# Power.net
KiCad netlist of a schematic drawn in Altium Designer
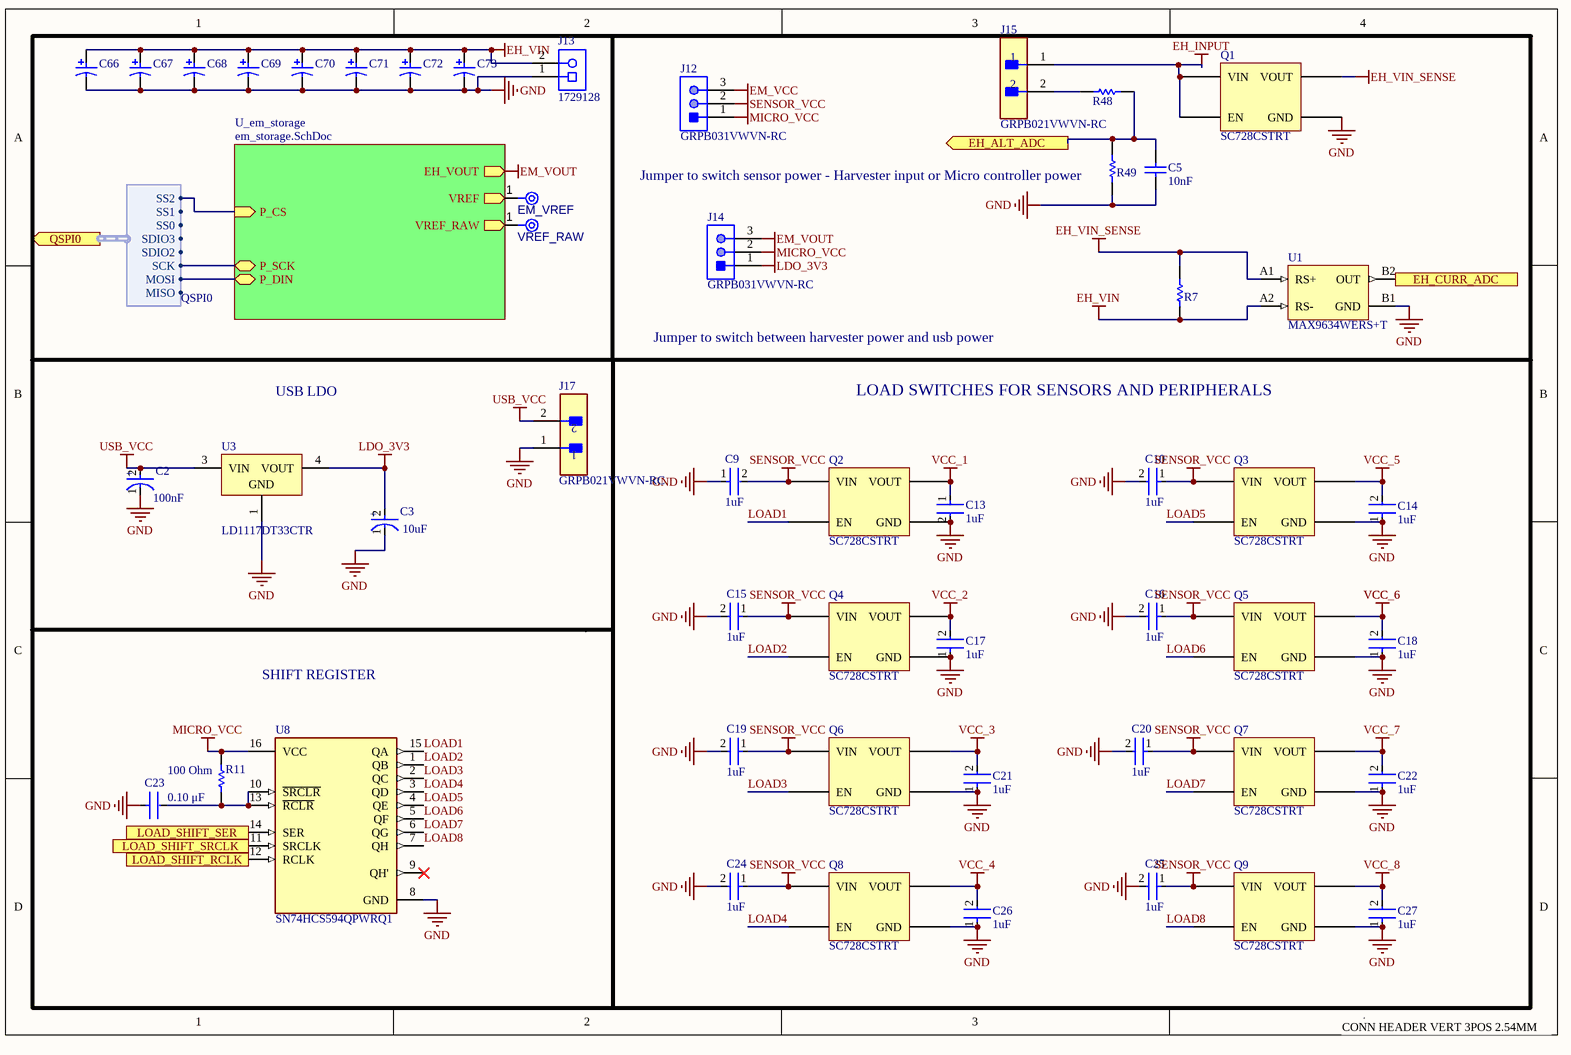
[diagram p0: Power.SchDoc]

(export (version "E")
  (design (tool "Eeschema 10.0.6"))
  (components
    (comp (ref "C2")
      (value "T491A104K035AT")
      (footprint "FP-T491A104K035AT-MFG")
      (description "CAP TANT 0.1UF 10% 35V 1206")
      (fields
        (field (name "TOLERANCE") "10%")
        (field (name "VOLTAGE") "35V")
        (field (name "CAPACITANCE") "100nF")
      )
      (libsource (lib "Altium Content Vault") (part "a00bbbee19879c290e62620ae7e47b1"))
    )
    (comp (ref "C3")
      (value "TAJA106K006RNJ")
      (footprint "FP-TAJA-MFG")
      (description "10uF 6.3V  ±10% 4Ω 1206  SMD Tantalum Capacitor")
      (fields
        (field (name "CAPACITANCE") "10uF")
        (field (name "VOLTAGE") "6.3V")
        (field (name "TOLERANCE") "20%")
      )
      (libsource (lib "Altium Content Vault") (part "203bc49f2ac43e59fd269a8c329ed05"))
    )
    (comp (ref "C5")
      (value "GRM188R71H103KA01D")
      (footprint "CAPC1608X90X35ML10T15")
      (description "Chip Capacitor, 10 nF, +/- 10%, 50 V, -55 to 125 degC, 0603 (1608 Metric), RoHS, Tape and Reel")
      (fields
        (field (name "VOLTAGE") "50V")
        (field (name "TOLERANCE") "10%")
        (field (name "CAPACITANCE") "10nF")
      )
      (libsource (lib "Altium Content Vault") (part "CAP-NP-2"))
    )
    (comp (ref "C9")
      (value "GRT155R61C105KE01J")
      (footprint "FP-GRM15-0_1-MFG")
      (description "CAP CER 1UF 10V X5R 0402")
      (fields
        (field (name "OCTOPART") "https://octopart.com/grm155r61a105ke15d-murata-197442")
        (field (name "MANUFACTURER PART NUMBER") "GRM155R61A105KE15D")
        (field (name "CAPACITANCE") "1uF")
      )
      (libsource (lib "Altium Content Vault") (part "02cd4be3c70576c341d710602a673aa"))
    )
    (comp (ref "C10")
      (value "GRT155R61C105KE01J")
      (footprint "FP-GRM15-0_1-MFG")
      (description "CAP CER 1UF 10V X5R 0402")
      (fields
        (field (name "OCTOPART") "https://octopart.com/grm155r61a105ke15d-murata-197442")
        (field (name "MANUFACTURER PART NUMBER") "GRM155R61A105KE15D")
        (field (name "CAPACITANCE") "1uF")
      )
      (libsource (lib "Altium Content Vault") (part "02cd4be3c70576c341d710602a673aa"))
    )
    (comp (ref "C13")
      (value "GRT155R61C105KE01J")
      (footprint "FP-GRM15-0_1-MFG")
      (description "CAP CER 1UF 10V X5R 0402")
      (fields
        (field (name "OCTOPART") "https://octopart.com/grm155r61a105ke15d-murata-197442")
        (field (name "MANUFACTURER PART NUMBER") "GRM155R61A105KE15D")
        (field (name "CAPACITANCE") "1uF")
      )
      (libsource (lib "Altium Content Vault") (part "02cd4be3c70576c341d710602a673aa"))
    )
    (comp (ref "C14")
      (value "GRT155R61C105KE01J")
      (footprint "FP-GRM15-0_1-MFG")
      (description "CAP CER 1UF 10V X5R 0402")
      (fields
        (field (name "OCTOPART") "https://octopart.com/grm155r61a105ke15d-murata-197442")
        (field (name "MANUFACTURER PART NUMBER") "GRM155R61A105KE15D")
        (field (name "CAPACITANCE") "1uF")
      )
      (libsource (lib "Altium Content Vault") (part "02cd4be3c70576c341d710602a673aa"))
    )
    (comp (ref "C15")
      (value "GRT155R61C105KE01J")
      (footprint "FP-GRM15-0_1-MFG")
      (description "CAP CER 1UF 10V X5R 0402")
      (fields
        (field (name "OCTOPART") "https://octopart.com/grm155r61a105ke15d-murata-197442")
        (field (name "MANUFACTURER PART NUMBER") "GRM155R61A105KE15D")
        (field (name "CAPACITANCE") "1uF")
      )
      (libsource (lib "Altium Content Vault") (part "02cd4be3c70576c341d710602a673aa"))
    )
    (comp (ref "C16")
      (value "GRT155R61C105KE01J")
      (footprint "FP-GRM15-0_1-MFG")
      (description "CAP CER 1UF 10V X5R 0402")
      (fields
        (field (name "OCTOPART") "https://octopart.com/grm155r61a105ke15d-murata-197442")
        (field (name "MANUFACTURER PART NUMBER") "GRM155R61A105KE15D")
        (field (name "CAPACITANCE") "1uF")
      )
      (libsource (lib "Altium Content Vault") (part "02cd4be3c70576c341d710602a673aa"))
    )
    (comp (ref "C17")
      (value "GRT155R61C105KE01J")
      (footprint "FP-GRM15-0_1-MFG")
      (description "CAP CER 1UF 10V X5R 0402")
      (fields
        (field (name "OCTOPART") "https://octopart.com/grm155r61a105ke15d-murata-197442")
        (field (name "MANUFACTURER PART NUMBER") "GRM155R61A105KE15D")
        (field (name "CAPACITANCE") "1uF")
      )
      (libsource (lib "Altium Content Vault") (part "02cd4be3c70576c341d710602a673aa"))
    )
    (comp (ref "C18")
      (value "GRT155R61C105KE01J")
      (footprint "FP-GRM15-0_1-MFG")
      (description "CAP CER 1UF 10V X5R 0402")
      (fields
        (field (name "OCTOPART") "https://octopart.com/grm155r61a105ke15d-murata-197442")
        (field (name "MANUFACTURER PART NUMBER") "GRM155R61A105KE15D")
        (field (name "CAPACITANCE") "1uF")
      )
      (libsource (lib "Altium Content Vault") (part "02cd4be3c70576c341d710602a673aa"))
    )
    (comp (ref "C19")
      (value "GRT155R61C105KE01J")
      (footprint "FP-GRM15-0_1-MFG")
      (description "CAP CER 1UF 10V X5R 0402")
      (fields
        (field (name "OCTOPART") "https://octopart.com/grm155r61a105ke15d-murata-197442")
        (field (name "MANUFACTURER PART NUMBER") "GRM155R61A105KE15D")
        (field (name "CAPACITANCE") "1uF")
      )
      (libsource (lib "Altium Content Vault") (part "02cd4be3c70576c341d710602a673aa"))
    )
    (comp (ref "C20")
      (value "GRT155R61C105KE01J")
      (footprint "FP-GRM15-0_1-MFG")
      (description "CAP CER 1UF 10V X5R 0402")
      (fields
        (field (name "OCTOPART") "https://octopart.com/grm155r61a105ke15d-murata-197442")
        (field (name "MANUFACTURER PART NUMBER") "GRM155R61A105KE15D")
        (field (name "CAPACITANCE") "1uF")
      )
      (libsource (lib "Altium Content Vault") (part "02cd4be3c70576c341d710602a673aa"))
    )
    (comp (ref "C21")
      (value "GRT155R61C105KE01J")
      (footprint "FP-GRM15-0_1-MFG")
      (description "CAP CER 1UF 10V X5R 0402")
      (fields
        (field (name "OCTOPART") "https://octopart.com/grm155r61a105ke15d-murata-197442")
        (field (name "MANUFACTURER PART NUMBER") "GRM155R61A105KE15D")
        (field (name "CAPACITANCE") "1uF")
      )
      (libsource (lib "Altium Content Vault") (part "02cd4be3c70576c341d710602a673aa"))
    )
    (comp (ref "C22")
      (value "GRT155R61C105KE01J")
      (footprint "FP-GRM15-0_1-MFG")
      (description "CAP CER 1UF 10V X5R 0402")
      (fields
        (field (name "OCTOPART") "https://octopart.com/grm155r61a105ke15d-murata-197442")
        (field (name "MANUFACTURER PART NUMBER") "GRM155R61A105KE15D")
        (field (name "CAPACITANCE") "1uF")
      )
      (libsource (lib "Altium Content Vault") (part "02cd4be3c70576c341d710602a673aa"))
    )
    (comp (ref "C23")
      (value "C0402C104K8PACTU")
      (footprint "FP-C0402-BB-MFG")
      (description "CAP CER 0.1UF 10V X5R 0402")
      (fields
        (field (name "CAPACITANCE") "0.10 μF")
        (field (name "MANUFACTURER") "Kemet")
        (field (name "TOLERANCE") "0.1")
      )
      (libsource (lib "Altium Content Vault") (part "b4654b650e69147ec39a6b967a45e02"))
    )
    (comp (ref "C24")
      (value "GRT155R61C105KE01J")
      (footprint "FP-GRM15-0_1-MFG")
      (description "CAP CER 1UF 10V X5R 0402")
      (fields
        (field (name "OCTOPART") "https://octopart.com/grm155r61a105ke15d-murata-197442")
        (field (name "MANUFACTURER PART NUMBER") "GRM155R61A105KE15D")
        (field (name "CAPACITANCE") "1uF")
      )
      (libsource (lib "Altium Content Vault") (part "02cd4be3c70576c341d710602a673aa"))
    )
    (comp (ref "C25")
      (value "GRT155R61C105KE01J")
      (footprint "FP-GRM15-0_1-MFG")
      (description "CAP CER 1UF 10V X5R 0402")
      (fields
        (field (name "OCTOPART") "https://octopart.com/grm155r61a105ke15d-murata-197442")
        (field (name "MANUFACTURER PART NUMBER") "GRM155R61A105KE15D")
        (field (name "CAPACITANCE") "1uF")
      )
      (libsource (lib "Altium Content Vault") (part "02cd4be3c70576c341d710602a673aa"))
    )
    (comp (ref "C26")
      (value "GRT155R61C105KE01J")
      (footprint "FP-GRM15-0_1-MFG")
      (description "CAP CER 1UF 10V X5R 0402")
      (fields
        (field (name "OCTOPART") "https://octopart.com/grm155r61a105ke15d-murata-197442")
        (field (name "MANUFACTURER PART NUMBER") "GRM155R61A105KE15D")
        (field (name "CAPACITANCE") "1uF")
      )
      (libsource (lib "Altium Content Vault") (part "02cd4be3c70576c341d710602a673aa"))
    )
    (comp (ref "C27")
      (value "GRT155R61C105KE01J")
      (footprint "FP-GRM15-0_1-MFG")
      (description "CAP CER 1UF 10V X5R 0402")
      (fields
        (field (name "OCTOPART") "https://octopart.com/grm155r61a105ke15d-murata-197442")
        (field (name "MANUFACTURER PART NUMBER") "GRM155R61A105KE15D")
        (field (name "CAPACITANCE") "1uF")
      )
      (libsource (lib "Altium Content Vault") (part "02cd4be3c70576c341d710602a673aa"))
    )
    (comp (ref "C66")
      (value "T491D106K025AT")
      (footprint "KEMT-T491-D_L")
      (description "Tantalum Capacitor, 10 uF, +/- 10%, 25 V, -55 to 125 degC, 2-Pin SMD, RoHS, Tape and Reel")
      (fields (field (name "MANUFACTURER") "Kemet") (field (name "VOLTAGE") "25VDC"))
      (libsource (lib "Altium Content Vault") (part "CAP-P-2"))
    )
    (comp (ref "C67")
      (value "T491D106K025AT")
      (footprint "KEMT-T491-D_L")
      (description "Tantalum Capacitor, 10 uF, +/- 10%, 25 V, -55 to 125 degC, 2-Pin SMD, RoHS, Tape and Reel")
      (fields (field (name "MANUFACTURER") "Kemet") (field (name "VOLTAGE") "25VDC"))
      (libsource (lib "Altium Content Vault") (part "CAP-P-2"))
    )
    (comp (ref "C68")
      (value "T491D106K025AT")
      (footprint "KEMT-T491-D_L")
      (description "Tantalum Capacitor, 10 uF, +/- 10%, 25 V, -55 to 125 degC, 2-Pin SMD, RoHS, Tape and Reel")
      (fields (field (name "MANUFACTURER") "Kemet") (field (name "VOLTAGE") "25VDC"))
      (libsource (lib "Altium Content Vault") (part "CAP-P-2"))
    )
    (comp (ref "C69")
      (value "T491D106K025AT")
      (footprint "KEMT-T491-D_L")
      (description "Tantalum Capacitor, 10 uF, +/- 10%, 25 V, -55 to 125 degC, 2-Pin SMD, RoHS, Tape and Reel")
      (fields (field (name "MANUFACTURER") "Kemet") (field (name "VOLTAGE") "25VDC"))
      (libsource (lib "Altium Content Vault") (part "CAP-P-2"))
    )
    (comp (ref "C70")
      (value "T491D106K025AT")
      (footprint "KEMT-T491-D_L")
      (description "Tantalum Capacitor, 10 uF, +/- 10%, 25 V, -55 to 125 degC, 2-Pin SMD, RoHS, Tape and Reel")
      (fields (field (name "MANUFACTURER") "Kemet") (field (name "VOLTAGE") "25VDC"))
      (libsource (lib "Altium Content Vault") (part "CAP-P-2"))
    )
    (comp (ref "C71")
      (value "T491D106K025AT")
      (footprint "KEMT-T491-D_L")
      (description "Tantalum Capacitor, 10 uF, +/- 10%, 25 V, -55 to 125 degC, 2-Pin SMD, RoHS, Tape and Reel")
      (fields (field (name "MANUFACTURER") "Kemet") (field (name "VOLTAGE") "25VDC"))
      (libsource (lib "Altium Content Vault") (part "CAP-P-2"))
    )
    (comp (ref "C72")
      (value "T491D106K025AT")
      (footprint "KEMT-T491-D_L")
      (description "Tantalum Capacitor, 10 uF, +/- 10%, 25 V, -55 to 125 degC, 2-Pin SMD, RoHS, Tape and Reel")
      (fields (field (name "MANUFACTURER") "Kemet") (field (name "VOLTAGE") "25VDC"))
      (libsource (lib "Altium Content Vault") (part "CAP-P-2"))
    )
    (comp (ref "C73")
      (value "T491D106K025AT")
      (footprint "KEMT-T491-D_L")
      (description "Tantalum Capacitor, 10 uF, +/- 10%, 25 V, -55 to 125 degC, 2-Pin SMD, RoHS, Tape and Reel")
      (fields (field (name "MANUFACTURER") "Kemet") (field (name "VOLTAGE") "25VDC"))
      (libsource (lib "Altium Content Vault") (part "CAP-P-2"))
    )
    (comp (ref "EM_VREF")
      (value "TPAD6R")
      (footprint "TP06R")
      (description "0.6mm round")
      (libsource (lib "Supersensor") (part "CMP-001-0001-4"))
    )
    (comp (ref "J12")
      (value "GRPB031VWVN-RC")
      (footprint "SLIN-GRPB031VWVN-RC_V")
      (fields (field (name "MANUFACTURER") "Sullins"))
      (libsource (lib "Altium Content Vault") (part "CN-1P-M-R3"))
    )
    (comp (ref "J13")
      (value "1729128")
      (footprint "PHOE-1729128-2_V")
      (description "PCB Terminal Block, 13.5 A, 400 V, 2-Pin THD, RoHS, Bulk")
      (fields (field (name "MANUFACTURER") "Phoenix Contact"))
      (libsource (lib "Altium Content Vault") (part "CN-2P-F-R2"))
    )
    (comp (ref "J14")
      (value "GRPB031VWVN-RC")
      (footprint "SLIN-GRPB031VWVN-RC_V")
      (fields (field (name "MANUFACTURER") "Sullins"))
      (libsource (lib "Altium Content Vault") (part "CN-1P-M-R3"))
    )
    (comp (ref "J15")
      (value "GRPB021VWVN-RC")
      (footprint "FP-GRPB021VWVN-RC-MFG")
      (description "CONN HEADER VERT 2POS 1.27MM")
      (libsource (lib "") (part "3bc925449376181038e59eaffc5286c_1"))
    )
    (comp (ref "J17")
      (value "GRPB021VWVN-RC")
      (footprint "FP-GRPB021VWVN-RC-MFG")
      (description "CONN HEADER VERT 2POS 1.27MM")
      (libsource (lib "Altium Content Vault") (part "3bc925449376181038e59eaffc5286c"))
    )
    (comp (ref "Q1")
      (value "SC728CSTRT")
      (footprint "PCBComponent_1")
      (libsource (lib "Integrated_Library1") (part "SC728CSTRT"))
    )
    (comp (ref "Q2")
      (value "SC728CSTRT")
      (footprint "PCBComponent_1")
      (libsource (lib "Integrated_Library1") (part "SC728CSTRT"))
    )
    (comp (ref "Q3")
      (value "SC728CSTRT")
      (footprint "PCBComponent_1")
      (libsource (lib "Integrated_Library1") (part "SC728CSTRT"))
    )
    (comp (ref "Q4")
      (value "SC728CSTRT")
      (footprint "PCBComponent_1")
      (libsource (lib "Integrated_Library1") (part "SC728CSTRT"))
    )
    (comp (ref "Q5")
      (value "SC728CSTRT")
      (footprint "PCBComponent_1")
      (libsource (lib "Integrated_Library1") (part "SC728CSTRT"))
    )
    (comp (ref "Q6")
      (value "SC728CSTRT")
      (footprint "PCBComponent_1")
      (libsource (lib "Integrated_Library1") (part "SC728CSTRT"))
    )
    (comp (ref "Q7")
      (value "SC728CSTRT")
      (footprint "PCBComponent_1")
      (libsource (lib "Integrated_Library1") (part "SC728CSTRT"))
    )
    (comp (ref "Q8")
      (value "SC728CSTRT")
      (footprint "PCBComponent_1")
      (libsource (lib "Integrated_Library1") (part "SC728CSTRT"))
    )
    (comp (ref "Q9")
      (value "SC728CSTRT")
      (footprint "PCBComponent_1")
      (libsource (lib "Integrated_Library1") (part "SC728CSTRT"))
    )
    (comp (ref "R7")
      (value "WSL0603R0300FEA18")
      (footprint "RESC1508X46X38ML25T25")
      (fields (field (name "MANUFACTURER") "Vishay Dale"))
      (libsource (lib "Altium Content Vault") (part "RES"))
    )
    (comp (ref "R11")
      (value "ERJ-2RKF1000X")
      (footprint "RESC1005X40X25LL05T05")
      (description "Chip Resistor, 100 Ohm, +/- 1%, 100 mW, -55 to 155 degC, 0402 (1005 Metric), RoHS, Tape and Reel")
      (fields
        (field (name "MANUFACTURER") "Basic Passives")
        (field (name "TOLERANCE") "1%")
        (field (name "RESISTANCE") "100 Ohm")
      )
      (libsource (lib "Altium Content Vault") (part "RES-2"))
    )
    (comp (ref "R48")
      (value "RC0402FR-071ML")
      (footprint "RESC1005X40X25NL05T10")
      (description "3M ohm")
      (fields (field (name "MANUFACTURER") "Yageo / Phycomp"))
      (libsource (lib "Altium Content Vault") (part "RES"))
    )
    (comp (ref "R49")
      (value "RC0402FR-071ML")
      (footprint "RESC1005X40X25NL05T10")
      (description "1M ohm")
      (fields (field (name "MANUFACTURER") "Yageo / Phycomp"))
      (libsource (lib "Altium Content Vault") (part "RES"))
    )
    (comp (ref "U1")
      (value "MAX9634WERS+T")
      (footprint "MAXM-R41A1+1")
      (libsource (lib "Altium Content Vault") (part "MAX9938_9634-X4"))
    )
    (comp (ref "U3")
      (value "LD1117DT33CTR")
      (footprint "TO-252_N")
      (description "Fixed Low Drop Positive Voltage Regulator, 3.3V, 3-Pin DPAK, Tape and Reel")
      (libsource (lib "Altium Content Vault") (part "PM-REG-LD1117-SOT3"))
    )
    (comp (ref "U8")
      (value "SN74HCS594QPWRQ1")
      (footprint "FP-PW0016A-IPC_A")
      (description "AUTOMOTIVE 8-BIT SHIFT REGISTERS")
      (libsource (lib "Altium Content Vault") (part "ee4c9120f52ff91501c7aa2bff67eb2"))
    )
    (comp (ref "VREF_RAW")
      (value "TPAD6R")
      (footprint "TP06R")
      (description "0.6mm round")
      (libsource (lib "Supersensor") (part "CMP-001-0001-4"))
    )
  )
  (nets
    (net (code "2") (name "/EH_ALT_ADC") (class "Default")
      (node (ref "C5") (pin "2") (pinfunction "2_2") (pintype "passive"))
      (node (ref "R48") (pin "1") (pinfunction "1_1") (pintype "passive"))
      (node (ref "R49") (pin "2") (pinfunction "2_2") (pintype "passive"))
    )
    (net (code "3") (name "/EH_CURR_ADC") (class "Default")
      (node (ref "U1") (pin "B2") (pinfunction "OUT_B2") (pintype "output"))
    )
    (net (code "4") (name "/LOAD1") (class "Default")
      (node (ref "Q2") (pin "B2") (pinfunction "EN_B2") (pintype "passive"))
      (node (ref "U8") (pin "15") (pinfunction "QA_15") (pintype "output"))
    )
    (net (code "5") (name "/LOAD2") (class "Default")
      (node (ref "Q4") (pin "B2") (pinfunction "EN_B2") (pintype "passive"))
      (node (ref "U8") (pin "1") (pinfunction "QB_1") (pintype "output"))
    )
    (net (code "6") (name "/LOAD3") (class "Default")
      (node (ref "Q6") (pin "B2") (pinfunction "EN_B2") (pintype "passive"))
      (node (ref "U8") (pin "2") (pinfunction "QC_2") (pintype "output"))
    )
    (net (code "7") (name "/LOAD4") (class "Default")
      (node (ref "Q8") (pin "B2") (pinfunction "EN_B2") (pintype "passive"))
      (node (ref "U8") (pin "3") (pinfunction "QD_3") (pintype "output"))
    )
    (net (code "8") (name "/LOAD5") (class "Default")
      (node (ref "Q3") (pin "B2") (pinfunction "EN_B2") (pintype "passive"))
      (node (ref "U8") (pin "4") (pinfunction "QE_4") (pintype "output"))
    )
    (net (code "9") (name "/LOAD6") (class "Default")
      (node (ref "Q5") (pin "B2") (pinfunction "EN_B2") (pintype "passive"))
      (node (ref "U8") (pin "5") (pinfunction "QF_5") (pintype "output"))
    )
    (net (code "10") (name "/LOAD7") (class "Default")
      (node (ref "Q7") (pin "B2") (pinfunction "EN_B2") (pintype "passive"))
      (node (ref "U8") (pin "6") (pinfunction "QG_6") (pintype "output"))
    )
    (net (code "11") (name "/LOAD8") (class "Default")
      (node (ref "Q9") (pin "B2") (pinfunction "EN_B2") (pintype "passive"))
      (node (ref "U8") (pin "7") (pinfunction "QH_7") (pintype "output"))
    )
    (net (code "12") (name "/LOAD_SHIFT_RCLK") (class "Default")
      (node (ref "U8") (pin "12") (pinfunction "RCLK_12") (pintype "input"))
    )
    (net (code "13") (name "/LOAD_SHIFT_SER") (class "Default")
      (node (ref "U8") (pin "14") (pinfunction "SER_14") (pintype "input"))
    )
    (net (code "14") (name "/LOAD_SHIFT_SRCLK") (class "Default")
      (node (ref "U8") (pin "11") (pinfunction "SRCLK_11") (pintype "input"))
    )
    (net (code "18") (name "/VREF") (class "Default")
      (node (ref "EM_VREF") (pin "1") (pinfunction "TP_1") (pintype "passive"))
    )
    (net (code "19") (name "/VREF_RAW") (class "Default")
      (node (ref "VREF_RAW") (pin "1") (pinfunction "TP_1") (pintype "passive"))
    )
    (net (code "21") (name "EH_INPUT") (class "Default")
      (node (ref "J15") (pin "1") (pinfunction "1_1") (pintype "passive"))
      (node (ref "Q1") (pin "A2") (pinfunction "VIN_A2") (pintype "passive"))
      (node (ref "Q1") (pin "B2") (pinfunction "EN_B2") (pintype "passive"))
    )
    (net (code "22") (name "EH_VIN") (class "Default")
      (node (ref "C66") (pin "1") (pinfunction "1_1") (pintype "passive"))
      (node (ref "C67") (pin "1") (pinfunction "1_1") (pintype "passive"))
      (node (ref "C68") (pin "1") (pinfunction "1_1") (pintype "passive"))
      (node (ref "C69") (pin "1") (pinfunction "1_1") (pintype "passive"))
      (node (ref "C70") (pin "1") (pinfunction "1_1") (pintype "passive"))
      (node (ref "C71") (pin "1") (pinfunction "1_1") (pintype "passive"))
      (node (ref "C72") (pin "1") (pinfunction "1_1") (pintype "passive"))
      (node (ref "C73") (pin "1") (pinfunction "1_1") (pintype "passive"))
      (node (ref "J13") (pin "2") (pinfunction "2_2") (pintype "passive"))
      (node (ref "R7") (pin "1") (pinfunction "1_1") (pintype "passive"))
      (node (ref "U1") (pin "A2") (pinfunction "RS-_A2") (pintype "input"))
    )
    (net (code "23") (name "EH_VIN_SENSE") (class "Default")
      (node (ref "Q1") (pin "A1") (pinfunction "VOUT_A1") (pintype "passive"))
      (node (ref "R7") (pin "2") (pinfunction "2_2") (pintype "passive"))
      (node (ref "U1") (pin "A1") (pinfunction "RS+_A1") (pintype "input"))
    )
    (net (code "24") (name "EM_VCC") (class "Default")
      (node (ref "J12") (pin "3") (pinfunction "3_3") (pintype "passive"))
    )
    (net (code "25") (name "EM_VOUT") (class "Default")
      (node (ref "J14") (pin "3") (pinfunction "3_3") (pintype "passive"))
    )
    (net (code "26") (name "GND") (class "Default")
      (node (ref "C10") (pin "2") (pinfunction "2_2") (pintype "passive"))
      (node (ref "C13") (pin "2") (pinfunction "2_2") (pintype "passive"))
      (node (ref "C14") (pin "1") (pinfunction "1_1") (pintype "passive"))
      (node (ref "C15") (pin "2") (pinfunction "2_2") (pintype "passive"))
      (node (ref "C16") (pin "2") (pinfunction "2_2") (pintype "passive"))
      (node (ref "C17") (pin "1") (pinfunction "1_1") (pintype "passive"))
      (node (ref "C18") (pin "1") (pinfunction "1_1") (pintype "passive"))
      (node (ref "C19") (pin "2") (pinfunction "2_2") (pintype "passive"))
      (node (ref "C2") (pin "1") (pinfunction "C_1") (pintype "passive"))
      (node (ref "C20") (pin "2") (pinfunction "2_2") (pintype "passive"))
      (node (ref "C21") (pin "1") (pinfunction "1_1") (pintype "passive"))
      (node (ref "C22") (pin "1") (pinfunction "1_1") (pintype "passive"))
      (node (ref "C23") (pin "1") (pinfunction "1_1") (pintype "passive"))
      (node (ref "C24") (pin "2") (pinfunction "2_2") (pintype "passive"))
      (node (ref "C25") (pin "2") (pinfunction "2_2") (pintype "passive"))
      (node (ref "C26") (pin "1") (pinfunction "1_1") (pintype "passive"))
      (node (ref "C27") (pin "1") (pinfunction "1_1") (pintype "passive"))
      (node (ref "C3") (pin "1") (pinfunction "C_1") (pintype "passive"))
      (node (ref "C5") (pin "1") (pinfunction "1_1") (pintype "passive"))
      (node (ref "C66") (pin "2") (pinfunction "2_2") (pintype "passive"))
      (node (ref "C67") (pin "2") (pinfunction "2_2") (pintype "passive"))
      (node (ref "C68") (pin "2") (pinfunction "2_2") (pintype "passive"))
      (node (ref "C69") (pin "2") (pinfunction "2_2") (pintype "passive"))
      (node (ref "C70") (pin "2") (pinfunction "2_2") (pintype "passive"))
      (node (ref "C71") (pin "2") (pinfunction "2_2") (pintype "passive"))
      (node (ref "C72") (pin "2") (pinfunction "2_2") (pintype "passive"))
      (node (ref "C73") (pin "2") (pinfunction "2_2") (pintype "passive"))
      (node (ref "C9") (pin "1") (pinfunction "1_1") (pintype "passive"))
      (node (ref "J13") (pin "1") (pinfunction "1_1") (pintype "passive"))
      (node (ref "J17") (pin "1") (pinfunction "1_1") (pintype "passive"))
      (node (ref "Q1") (pin "B1") (pinfunction "GND_B1") (pintype "passive"))
      (node (ref "Q2") (pin "B1") (pinfunction "GND_B1") (pintype "passive"))
      (node (ref "Q3") (pin "B1") (pinfunction "GND_B1") (pintype "passive"))
      (node (ref "Q4") (pin "B1") (pinfunction "GND_B1") (pintype "passive"))
      (node (ref "Q5") (pin "B1") (pinfunction "GND_B1") (pintype "passive"))
      (node (ref "Q6") (pin "B1") (pinfunction "GND_B1") (pintype "passive"))
      (node (ref "Q7") (pin "B1") (pinfunction "GND_B1") (pintype "passive"))
      (node (ref "Q8") (pin "B1") (pinfunction "GND_B1") (pintype "passive"))
      (node (ref "Q9") (pin "B1") (pinfunction "GND_B1") (pintype "passive"))
      (node (ref "R49") (pin "1") (pinfunction "1_1") (pintype "passive"))
      (node (ref "U1") (pin "B1") (pinfunction "GND_B1") (pintype "power_in"))
      (node (ref "U3") (pin "1") (pinfunction "GND_1") (pintype "power_in"))
      (node (ref "U8") (pin "8") (pinfunction "GND_8") (pintype "power_in"))
    )
    (net (code "27") (name "LDO_3V3") (class "Default")
      (node (ref "C3") (pin "2") (pinfunction "A_2") (pintype "passive"))
      (node (ref "J14") (pin "1") (pinfunction "1_1") (pintype "passive"))
      (node (ref "U3") (pin "4") (pinfunction "VOUT_4") (pintype "power_in"))
    )
    (net (code "28") (name "MICRO_VCC") (class "Default")
      (node (ref "J12") (pin "1") (pinfunction "1_1") (pintype "passive"))
      (node (ref "J14") (pin "2") (pinfunction "2_2") (pintype "passive"))
      (node (ref "R11") (pin "2") (pinfunction "2_2") (pintype "passive"))
      (node (ref "U8") (pin "16") (pinfunction "VCC_16") (pintype "power_in"))
    )
    (net (code "29") (name "Net-(J15-Pad2)") (class "Default")
      (node (ref "J15") (pin "2") (pinfunction "2_2") (pintype "passive"))
      (node (ref "R48") (pin "2") (pinfunction "2_2") (pintype "passive"))
    )
    (net (code "30") (name "Net-(U8-~{RCLR})") (class "Default")
      (node (ref "C23") (pin "2") (pinfunction "2_2") (pintype "passive"))
      (node (ref "R11") (pin "1") (pinfunction "1_1") (pintype "passive"))
      (node (ref "U8") (pin "10") (pinfunction "~{SRCLR}_10") (pintype "input"))
      (node (ref "U8") (pin "13") (pinfunction "~{RCLR}_13") (pintype "input"))
    )
    (net (code "31") (name "SENSOR_VCC") (class "Default")
      (node (ref "C10") (pin "1") (pinfunction "1_1") (pintype "passive"))
      (node (ref "C15") (pin "1") (pinfunction "1_1") (pintype "passive"))
      (node (ref "C16") (pin "1") (pinfunction "1_1") (pintype "passive"))
      (node (ref "C19") (pin "1") (pinfunction "1_1") (pintype "passive"))
      (node (ref "C20") (pin "1") (pinfunction "1_1") (pintype "passive"))
      (node (ref "C24") (pin "1") (pinfunction "1_1") (pintype "passive"))
      (node (ref "C25") (pin "1") (pinfunction "1_1") (pintype "passive"))
      (node (ref "C9") (pin "2") (pinfunction "2_2") (pintype "passive"))
      (node (ref "J12") (pin "2") (pinfunction "2_2") (pintype "passive"))
      (node (ref "Q2") (pin "A2") (pinfunction "VIN_A2") (pintype "passive"))
      (node (ref "Q3") (pin "A2") (pinfunction "VIN_A2") (pintype "passive"))
      (node (ref "Q4") (pin "A2") (pinfunction "VIN_A2") (pintype "passive"))
      (node (ref "Q5") (pin "A2") (pinfunction "VIN_A2") (pintype "passive"))
      (node (ref "Q6") (pin "A2") (pinfunction "VIN_A2") (pintype "passive"))
      (node (ref "Q7") (pin "A2") (pinfunction "VIN_A2") (pintype "passive"))
      (node (ref "Q8") (pin "A2") (pinfunction "VIN_A2") (pintype "passive"))
      (node (ref "Q9") (pin "A2") (pinfunction "VIN_A2") (pintype "passive"))
    )
    (net (code "32") (name "USB_VCC") (class "Default")
      (node (ref "C2") (pin "2") (pinfunction "A_2") (pintype "passive"))
      (node (ref "J17") (pin "2") (pinfunction "2_2") (pintype "passive"))
      (node (ref "U3") (pin "3") (pinfunction "VIN_3") (pintype "power_in"))
    )
    (net (code "33") (name "VCC_1") (class "Default")
      (node (ref "C13") (pin "1") (pinfunction "1_1") (pintype "passive"))
      (node (ref "Q2") (pin "A1") (pinfunction "VOUT_A1") (pintype "passive"))
    )
    (net (code "34") (name "VCC_2") (class "Default")
      (node (ref "C17") (pin "2") (pinfunction "2_2") (pintype "passive"))
      (node (ref "Q4") (pin "A1") (pinfunction "VOUT_A1") (pintype "passive"))
    )
    (net (code "35") (name "VCC_3") (class "Default")
      (node (ref "C21") (pin "2") (pinfunction "2_2") (pintype "passive"))
      (node (ref "Q6") (pin "A1") (pinfunction "VOUT_A1") (pintype "passive"))
    )
    (net (code "36") (name "VCC_4") (class "Default")
      (node (ref "C26") (pin "2") (pinfunction "2_2") (pintype "passive"))
      (node (ref "Q8") (pin "A1") (pinfunction "VOUT_A1") (pintype "passive"))
    )
    (net (code "37") (name "VCC_5") (class "Default")
      (node (ref "C14") (pin "2") (pinfunction "2_2") (pintype "passive"))
      (node (ref "Q3") (pin "A1") (pinfunction "VOUT_A1") (pintype "passive"))
    )
    (net (code "38") (name "VCC_6") (class "Default")
      (node (ref "C18") (pin "2") (pinfunction "2_2") (pintype "passive"))
      (node (ref "Q5") (pin "A1") (pinfunction "VOUT_A1") (pintype "passive"))
    )
    (net (code "39") (name "VCC_7") (class "Default")
      (node (ref "C22") (pin "2") (pinfunction "2_2") (pintype "passive"))
      (node (ref "Q7") (pin "A1") (pinfunction "VOUT_A1") (pintype "passive"))
    )
    (net (code "40") (name "VCC_8") (class "Default")
      (node (ref "C27") (pin "2") (pinfunction "2_2") (pintype "passive"))
      (node (ref "Q9") (pin "A1") (pinfunction "VOUT_A1") (pintype "passive"))
    )
    (net (code "41") (name "unconnected-(U8-QH'-Pad9)") (class "Default")
      (node (ref "U8") (pin "9") (pinfunction "QH'_9") (pintype "output+no_connect"))
    )
  )
)
